# Sheet1.net
KiCad netlist of a schematic drawn in Altium Designer
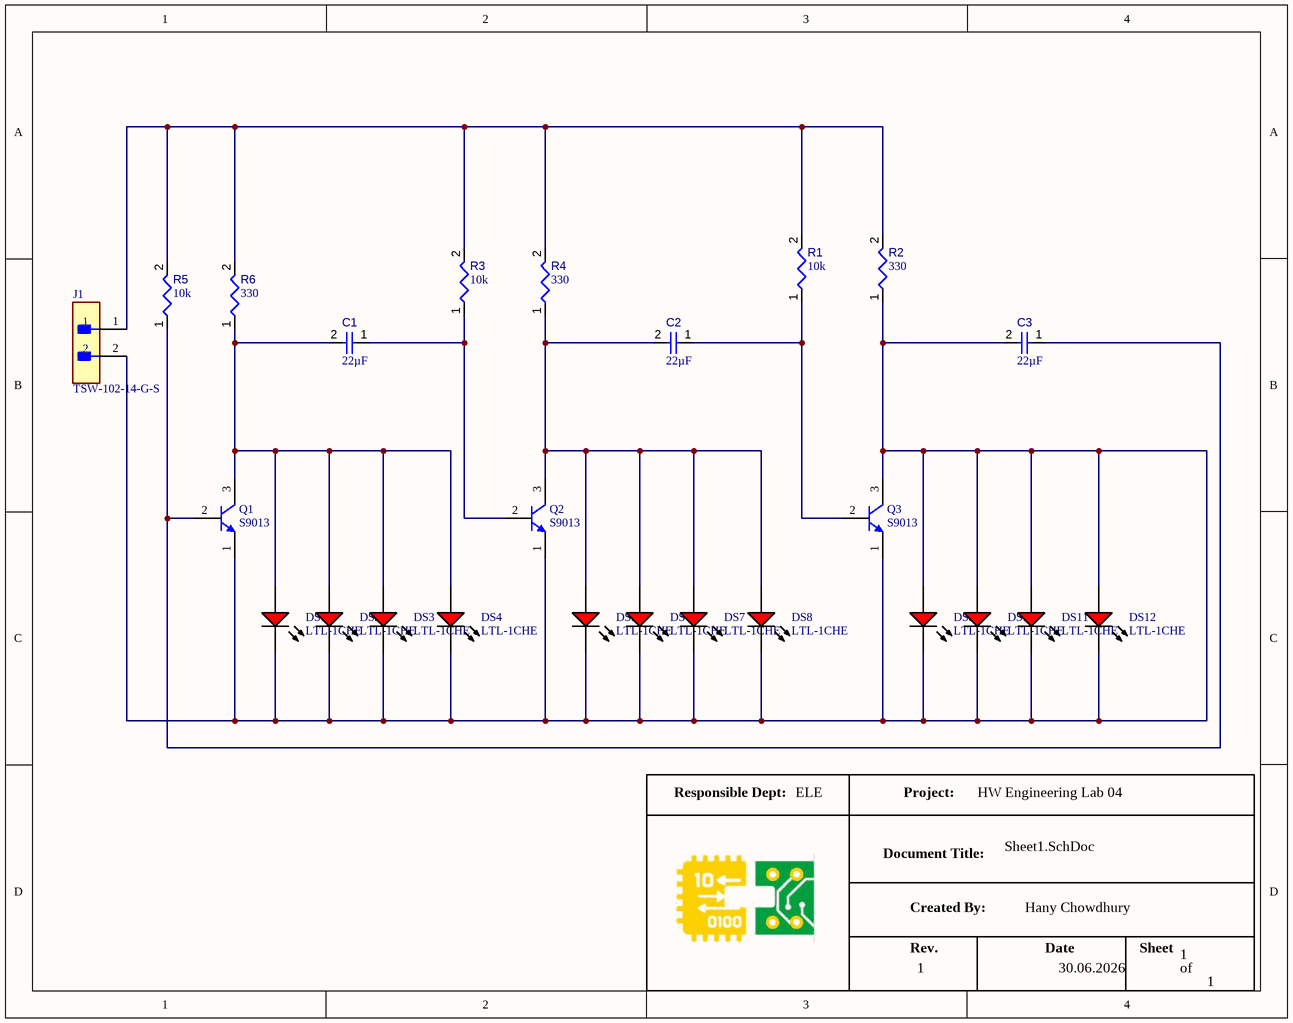
[diagram p0: Sheet1.SchDoc]

(export (version "E")
  (design (tool "Eeschema 10.0.6"))
  (components
    (comp (ref "C1")
      (value "22µF")
      (footprint "CAPC0805(2012)145_L")
      (description "Chip Capacitor, 22µF +/-40%, 16V, 0805, Thickness 1.45 mm")
      (fields (field (name "TOLERANCE") "5%") (field (name "Comment") "Capacitor 22µF +/-40% 16V 0805"))
      (libsource (lib "Hany Chowdhury") (part "CAP-NP-2"))
    )
    (comp (ref "C2")
      (value "22µF")
      (footprint "CAPC0805(2012)145_L")
      (description "Chip Capacitor, 22µF +/-40%, 16V, 0805, Thickness 1.45 mm")
      (fields (field (name "TOLERANCE") "5%") (field (name "Comment") "Capacitor 22µF +/-40% 16V 0805"))
      (libsource (lib "Hany Chowdhury") (part "CAP-NP-2"))
    )
    (comp (ref "C3")
      (value "22µF")
      (footprint "CAPC0805(2012)145_L")
      (description "Chip Capacitor, 22µF +/-40%, 16V, 0805, Thickness 1.45 mm")
      (fields (field (name "TOLERANCE") "5%") (field (name "Comment") "Capacitor 22µF +/-40% 16V 0805"))
      (libsource (lib "Hany Chowdhury") (part "CAP-NP-2"))
    )
    (comp (ref "DS1")
      (value "LTL-1CHE")
      (footprint "INDPR60-254-520X380X650")
      (description "LED Uni-Color Red, 100 mW, 30 mA, -55 to 100 degC, 2-Pin THD, RoHS, Bulk")
      (fields (field (name "MANUFACTURER") "Lite-On"))
      (libsource (lib "Hany Chowdhury") (part "LED-RED-AK-2"))
    )
    (comp (ref "DS2")
      (value "LTL-1CHE")
      (footprint "INDPR60-254-520X380X650")
      (description "LED Uni-Color Red, 100 mW, 30 mA, -55 to 100 degC, 2-Pin THD, RoHS, Bulk")
      (fields (field (name "MANUFACTURER") "Lite-On"))
      (libsource (lib "Hany Chowdhury") (part "LED-RED-AK-2"))
    )
    (comp (ref "DS3")
      (value "LTL-1CHE")
      (footprint "INDPR60-254-520X380X650")
      (description "LED Uni-Color Red, 100 mW, 30 mA, -55 to 100 degC, 2-Pin THD, RoHS, Bulk")
      (fields (field (name "MANUFACTURER") "Lite-On"))
      (libsource (lib "Hany Chowdhury") (part "LED-RED-AK-2"))
    )
    (comp (ref "DS4")
      (value "LTL-1CHE")
      (footprint "INDPR60-254-520X380X650")
      (description "LED Uni-Color Red, 100 mW, 30 mA, -55 to 100 degC, 2-Pin THD, RoHS, Bulk")
      (fields (field (name "MANUFACTURER") "Lite-On"))
      (libsource (lib "Hany Chowdhury") (part "LED-RED-AK-2"))
    )
    (comp (ref "DS5")
      (value "LTL-1CHE")
      (footprint "INDPR60-254-520X380X650")
      (description "LED Uni-Color Red, 100 mW, 30 mA, -55 to 100 degC, 2-Pin THD, RoHS, Bulk")
      (fields (field (name "MANUFACTURER") "Lite-On"))
      (libsource (lib "Hany Chowdhury") (part "LED-RED-AK-2"))
    )
    (comp (ref "DS6")
      (value "LTL-1CHE")
      (footprint "INDPR60-254-520X380X650")
      (description "LED Uni-Color Red, 100 mW, 30 mA, -55 to 100 degC, 2-Pin THD, RoHS, Bulk")
      (fields (field (name "MANUFACTURER") "Lite-On"))
      (libsource (lib "Hany Chowdhury") (part "LED-RED-AK-2"))
    )
    (comp (ref "DS7")
      (value "LTL-1CHE")
      (footprint "INDPR60-254-520X380X650")
      (description "LED Uni-Color Red, 100 mW, 30 mA, -55 to 100 degC, 2-Pin THD, RoHS, Bulk")
      (fields (field (name "MANUFACTURER") "Lite-On"))
      (libsource (lib "Hany Chowdhury") (part "LED-RED-AK-2"))
    )
    (comp (ref "DS8")
      (value "LTL-1CHE")
      (footprint "INDPR60-254-520X380X650")
      (description "LED Uni-Color Red, 100 mW, 30 mA, -55 to 100 degC, 2-Pin THD, RoHS, Bulk")
      (fields (field (name "MANUFACTURER") "Lite-On"))
      (libsource (lib "Hany Chowdhury") (part "LED-RED-AK-2"))
    )
    (comp (ref "DS9")
      (value "LTL-1CHE")
      (footprint "INDPR60-254-520X380X650")
      (description "LED Uni-Color Red, 100 mW, 30 mA, -55 to 100 degC, 2-Pin THD, RoHS, Bulk")
      (fields (field (name "MANUFACTURER") "Lite-On"))
      (libsource (lib "Hany Chowdhury") (part "LED-RED-AK-2"))
    )
    (comp (ref "DS10")
      (value "LTL-1CHE")
      (footprint "INDPR60-254-520X380X650")
      (description "LED Uni-Color Red, 100 mW, 30 mA, -55 to 100 degC, 2-Pin THD, RoHS, Bulk")
      (fields (field (name "MANUFACTURER") "Lite-On"))
      (libsource (lib "Hany Chowdhury") (part "LED-RED-AK-2"))
    )
    (comp (ref "DS11")
      (value "LTL-1CHE")
      (footprint "INDPR60-254-520X380X650")
      (description "LED Uni-Color Red, 100 mW, 30 mA, -55 to 100 degC, 2-Pin THD, RoHS, Bulk")
      (fields (field (name "MANUFACTURER") "Lite-On"))
      (libsource (lib "Hany Chowdhury") (part "LED-RED-AK-2"))
    )
    (comp (ref "DS12")
      (value "LTL-1CHE")
      (footprint "INDPR60-254-520X380X650")
      (description "LED Uni-Color Red, 100 mW, 30 mA, -55 to 100 degC, 2-Pin THD, RoHS, Bulk")
      (fields (field (name "MANUFACTURER") "Lite-On"))
      (libsource (lib "Hany Chowdhury") (part "LED-RED-AK-2"))
    )
    (comp (ref "J1")
      (value "TSW-102-14-G-S")
      (footprint "FP-TSW-102-14-G-S-MFG")
      (description "TSW - Samtec 2.54mm Pin Header 13.46mm Overall Pin Length 2.79mm Tail (14) - Fast Stock(mcv)")
      (libsource (lib "Hany Chowdhury") (part "88c1139f9d239099ffebecbe3f7647a"))
    )
    (comp (ref "Q1")
      (value "S9013")
      (footprint "JSCJ-TO-92-3_V")
      (description "Transistor, NPN, 0.1 uA, 150 MHz, 3-Pin TO-92")
      (fields (field (name "MANUFACTURER") "Jiangsu Changjiang Electronics Technology"))
      (libsource (lib "Hany Chowdhury") (part "BJT-NPN-EBC-3"))
    )
    (comp (ref "Q2")
      (value "S9013")
      (footprint "JSCJ-TO-92-3_V")
      (description "Transistor, NPN, 0.1 uA, 150 MHz, 3-Pin TO-92")
      (fields (field (name "MANUFACTURER") "Jiangsu Changjiang Electronics Technology"))
      (libsource (lib "Hany Chowdhury") (part "BJT-NPN-EBC-3"))
    )
    (comp (ref "Q3")
      (value "S9013")
      (footprint "JSCJ-TO-92-3_V")
      (description "Transistor, NPN, 0.1 uA, 150 MHz, 3-Pin TO-92")
      (fields (field (name "MANUFACTURER") "Jiangsu Changjiang Electronics Technology"))
      (libsource (lib "Hany Chowdhury") (part "BJT-NPN-EBC-3"))
    )
    (comp (ref "R1")
      (value "10k")
      (footprint "RESA60-630X240")
      (description "Axial Resistor, 10 KOhm, +/- 1%, 0.25 W, -55 to 155 degC, 2-Pin THD, RoHS, Bulk")
      (fields (field (name "TOLERANCE") "1%") (field (name "POWER") "250mW"))
      (libsource (lib "Hany Chowdhury") (part "RES-2"))
    )
    (comp (ref "R2")
      (value "330")
      (footprint "RESC0402(1005)_L")
      (description "Chip Resistor, 330 Ohms, +/-5 %, 63 mW, -55 to 155 degC, 0402")
      (fields (field (name "POWER") "63mW") (field (name "TOLERANCE") "5%"))
      (libsource (lib "Hany Chowdhury") (part "RES-2"))
    )
    (comp (ref "R3")
      (value "10k")
      (footprint "RESA60-630X240")
      (description "Axial Resistor, 10 KOhm, +/- 1%, 0.25 W, -55 to 155 degC, 2-Pin THD, RoHS, Bulk")
      (fields (field (name "TOLERANCE") "1%") (field (name "POWER") "250mW"))
      (libsource (lib "Hany Chowdhury") (part "RES-2"))
    )
    (comp (ref "R4")
      (value "330")
      (footprint "RESC0402(1005)_L")
      (description "Chip Resistor, 330 Ohms, +/-5 %, 63 mW, -55 to 155 degC, 0402")
      (fields (field (name "POWER") "63mW") (field (name "TOLERANCE") "5%"))
      (libsource (lib "Hany Chowdhury") (part "RES-2"))
    )
    (comp (ref "R5")
      (value "10k")
      (footprint "RESA60-630X240")
      (description "Axial Resistor, 10 KOhm, +/- 1%, 0.25 W, -55 to 155 degC, 2-Pin THD, RoHS, Bulk")
      (fields (field (name "TOLERANCE") "1%") (field (name "POWER") "250mW"))
      (libsource (lib "Hany Chowdhury") (part "RES-2"))
    )
    (comp (ref "R6")
      (value "330")
      (footprint "RESC0402(1005)_L")
      (description "Chip Resistor, 330 Ohms, +/-5 %, 63 mW, -55 to 155 degC, 0402")
      (fields (field (name "POWER") "63mW") (field (name "TOLERANCE") "5%"))
      (libsource (lib "Hany Chowdhury") (part "RES-2"))
    )
  )
  (nets
    (net (code "1") (name "Net-(DS1-A)") (class "Default")
      (node (ref "C1") (pin "2") (pinfunction "2_2") (pintype "passive"))
      (node (ref "DS1") (pin "1") (pinfunction "A_1") (pintype "passive"))
      (node (ref "DS2") (pin "1") (pinfunction "A_1") (pintype "passive"))
      (node (ref "DS3") (pin "1") (pinfunction "A_1") (pintype "passive"))
      (node (ref "DS4") (pin "1") (pinfunction "A_1") (pintype "passive"))
      (node (ref "Q1") (pin "3") (pinfunction "C_3") (pintype "passive"))
      (node (ref "R6") (pin "1") (pinfunction "1_1") (pintype "passive"))
    )
    (net (code "2") (name "Net-(DS1-K)") (class "Default")
      (node (ref "C3") (pin "2") (pinfunction "2_2") (pintype "passive"))
      (node (ref "DS1") (pin "2") (pinfunction "K_2") (pintype "passive"))
      (node (ref "DS10") (pin "1") (pinfunction "A_1") (pintype "passive"))
      (node (ref "DS10") (pin "2") (pinfunction "K_2") (pintype "passive"))
      (node (ref "DS11") (pin "1") (pinfunction "A_1") (pintype "passive"))
      (node (ref "DS11") (pin "2") (pinfunction "K_2") (pintype "passive"))
      (node (ref "DS12") (pin "1") (pinfunction "A_1") (pintype "passive"))
      (node (ref "DS12") (pin "2") (pinfunction "K_2") (pintype "passive"))
      (node (ref "DS2") (pin "2") (pinfunction "K_2") (pintype "passive"))
      (node (ref "DS3") (pin "2") (pinfunction "K_2") (pintype "passive"))
      (node (ref "DS4") (pin "2") (pinfunction "K_2") (pintype "passive"))
      (node (ref "DS5") (pin "2") (pinfunction "K_2") (pintype "passive"))
      (node (ref "DS6") (pin "2") (pinfunction "K_2") (pintype "passive"))
      (node (ref "DS7") (pin "2") (pinfunction "K_2") (pintype "passive"))
      (node (ref "DS8") (pin "2") (pinfunction "K_2") (pintype "passive"))
      (node (ref "DS9") (pin "1") (pinfunction "A_1") (pintype "passive"))
      (node (ref "DS9") (pin "2") (pinfunction "K_2") (pintype "passive"))
      (node (ref "J1") (pin "2") (pinfunction "2_2") (pintype "passive"))
      (node (ref "Q1") (pin "1") (pinfunction "E_1") (pintype "passive"))
      (node (ref "Q2") (pin "1") (pinfunction "E_1") (pintype "passive"))
      (node (ref "Q3") (pin "1") (pinfunction "E_1") (pintype "passive"))
      (node (ref "Q3") (pin "3") (pinfunction "C_3") (pintype "passive"))
      (node (ref "R2") (pin "1") (pinfunction "1_1") (pintype "passive"))
    )
    (net (code "3") (name "Net-(DS5-A)") (class "Default")
      (node (ref "C2") (pin "2") (pinfunction "2_2") (pintype "passive"))
      (node (ref "DS5") (pin "1") (pinfunction "A_1") (pintype "passive"))
      (node (ref "DS6") (pin "1") (pinfunction "A_1") (pintype "passive"))
      (node (ref "DS7") (pin "1") (pinfunction "A_1") (pintype "passive"))
      (node (ref "DS8") (pin "1") (pinfunction "A_1") (pintype "passive"))
      (node (ref "Q2") (pin "3") (pinfunction "C_3") (pintype "passive"))
      (node (ref "R4") (pin "1") (pinfunction "1_1") (pintype "passive"))
    )
    (net (code "4") (name "Net-(J1-Pad1)") (class "Default")
      (node (ref "J1") (pin "1") (pinfunction "1_1") (pintype "passive"))
      (node (ref "R1") (pin "2") (pinfunction "2_2") (pintype "passive"))
      (node (ref "R2") (pin "2") (pinfunction "2_2") (pintype "passive"))
      (node (ref "R3") (pin "2") (pinfunction "2_2") (pintype "passive"))
      (node (ref "R4") (pin "2") (pinfunction "2_2") (pintype "passive"))
      (node (ref "R5") (pin "2") (pinfunction "2_2") (pintype "passive"))
      (node (ref "R6") (pin "2") (pinfunction "2_2") (pintype "passive"))
    )
    (net (code "5") (name "Net-(Q1-B)") (class "Default")
      (node (ref "C3") (pin "1") (pinfunction "1_1") (pintype "passive"))
      (node (ref "Q1") (pin "2") (pinfunction "B_2") (pintype "passive"))
      (node (ref "R5") (pin "1") (pinfunction "1_1") (pintype "passive"))
    )
    (net (code "6") (name "Net-(Q2-B)") (class "Default")
      (node (ref "C1") (pin "1") (pinfunction "1_1") (pintype "passive"))
      (node (ref "Q2") (pin "2") (pinfunction "B_2") (pintype "passive"))
      (node (ref "R3") (pin "1") (pinfunction "1_1") (pintype "passive"))
    )
    (net (code "7") (name "Net-(Q3-B)") (class "Default")
      (node (ref "C2") (pin "1") (pinfunction "1_1") (pintype "passive"))
      (node (ref "Q3") (pin "2") (pinfunction "B_2") (pintype "passive"))
      (node (ref "R1") (pin "1") (pinfunction "1_1") (pintype "passive"))
    )
  )
)
